# CATv1.net
KiCad netlist of a schematic drawn in EAGLE
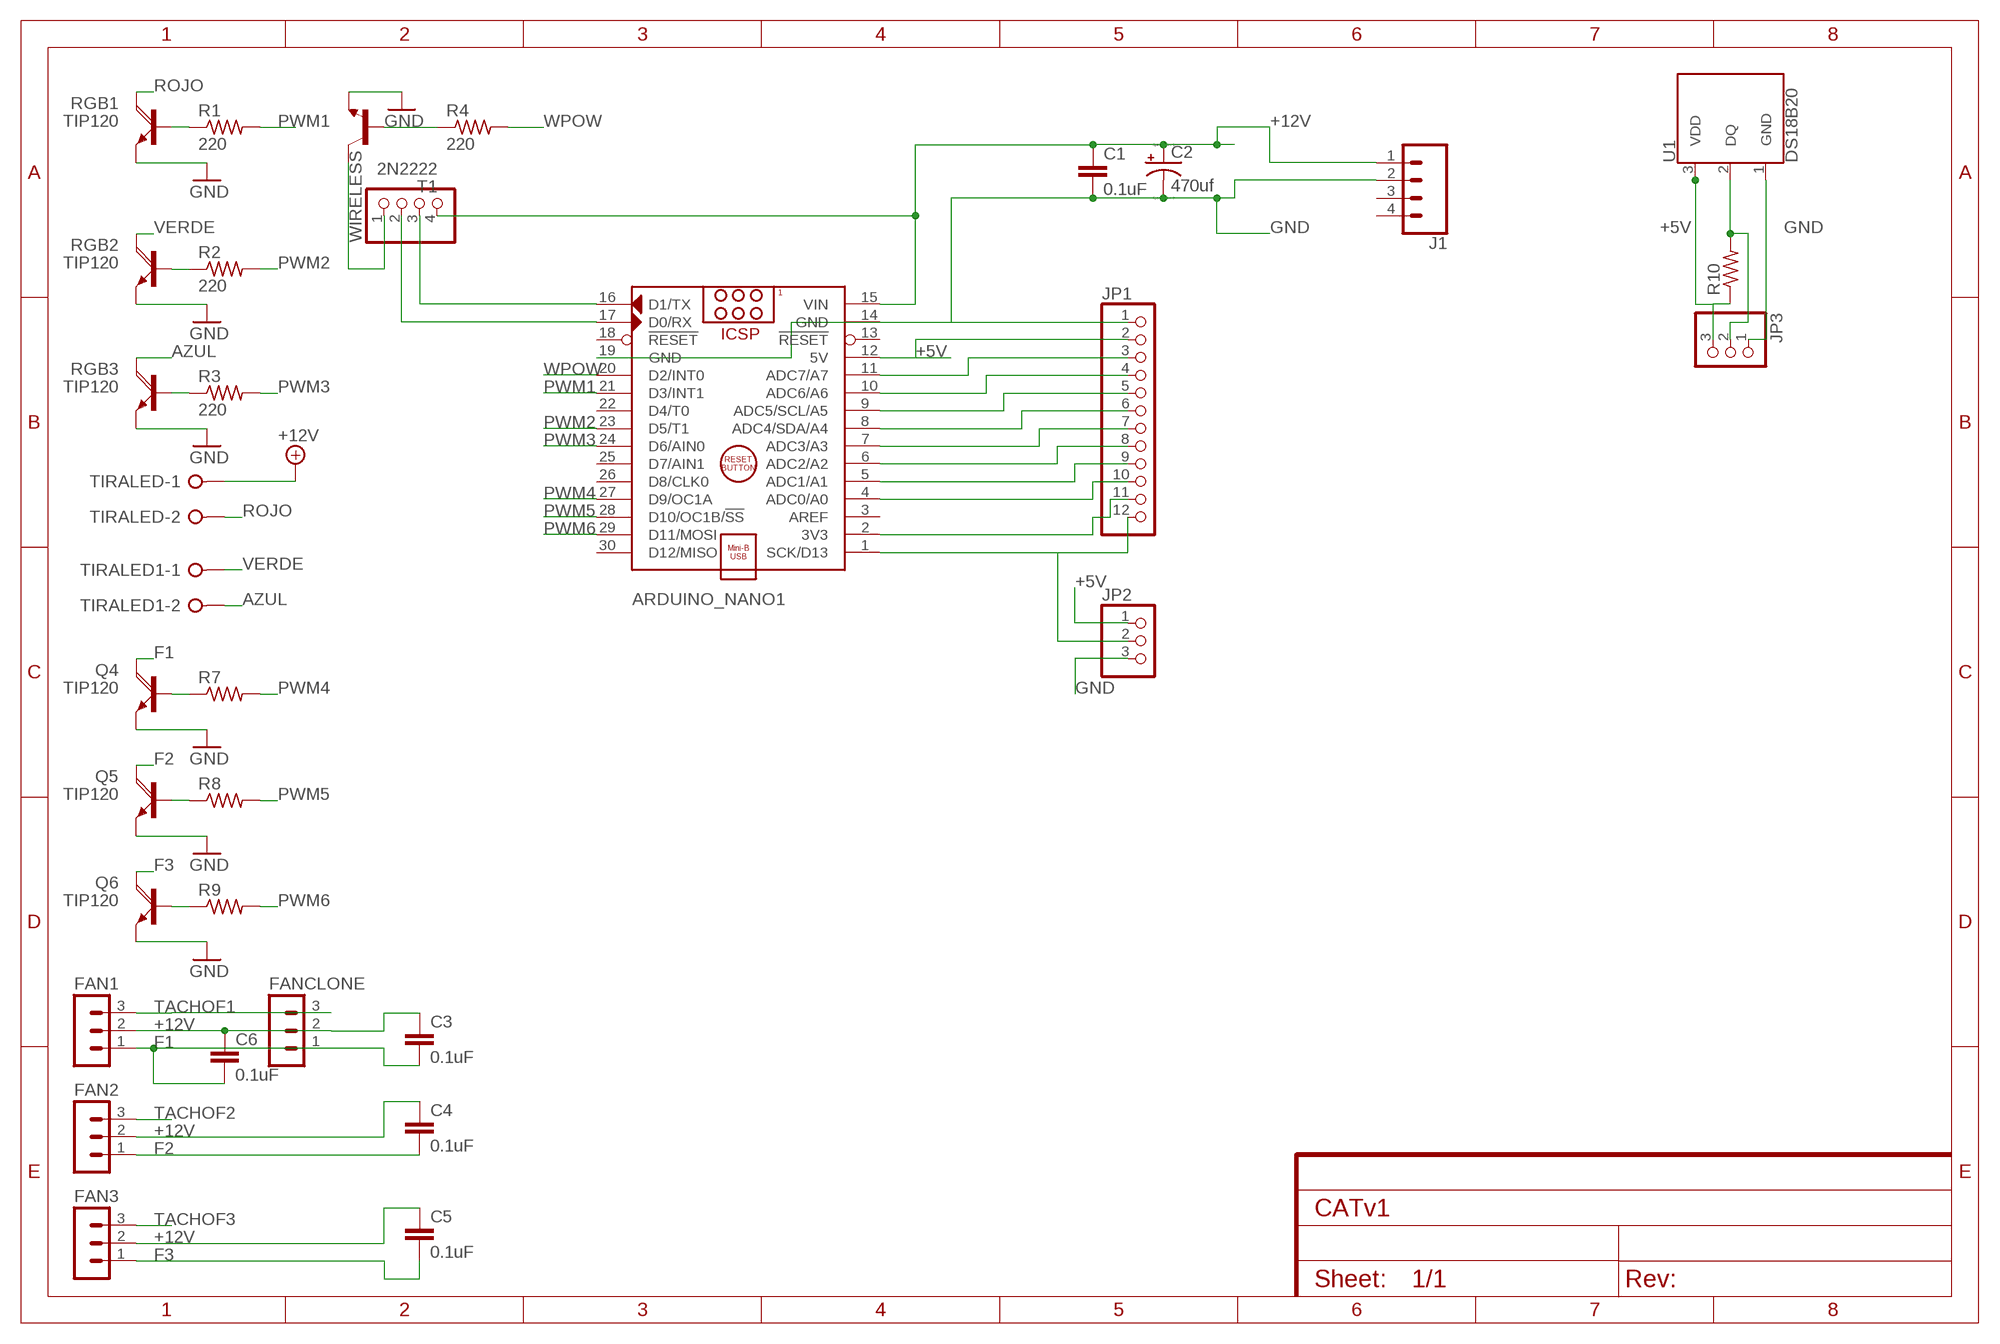
[diagram p0: schematic, sheet 1]

(export (version "E")
  (design (tool "Eeschema 10.0.6"))
  (components
    (comp (ref "ARDUINO_NANO1")
      (value "ARDUINO_NANO")
      (footprint "eagle-import:ARDUINO_NANO")
      (libsource (lib "eagle-import") (part "ARDUINO_NANO"))
    )
    (comp (ref "C1")
      (value "0.1uF")
      (footprint "eagle-import:CAP-PTH-SMALL-KIT")
      (libsource (lib "eagle-import") (part "0.1UF-KIT-EZ-50V-20%"))
    )
    (comp (ref "C2")
      (value "470uf")
      (footprint "eagle-import:E5-10,5")
      (libsource (lib "eagle-import") (part "CPOL-USE5-10.5"))
    )
    (comp (ref "C3")
      (value "0.1uF")
      (footprint "eagle-import:CAP-PTH-SMALL-KIT")
      (libsource (lib "eagle-import") (part "0.1UF-KIT-EZ-50V-20%"))
    )
    (comp (ref "C4")
      (value "0.1uF")
      (footprint "eagle-import:CAP-PTH-SMALL-KIT")
      (libsource (lib "eagle-import") (part "0.1UF-KIT-EZ-50V-20%"))
    )
    (comp (ref "C5")
      (value "0.1uF")
      (footprint "eagle-import:CAP-PTH-SMALL-KIT")
      (libsource (lib "eagle-import") (part "0.1UF-KIT-EZ-50V-20%"))
    )
    (comp (ref "C6")
      (value "0.1uF")
      (footprint "eagle-import:CAP-PTH-SMALL-KIT")
      (libsource (lib "eagle-import") (part "0.1UF-KIT-EZ-50V-20%"))
    )
    (comp (ref "FAN1")
      (value "MA03-1")
      (footprint "eagle-import:MA03-1")
      (libsource (lib "eagle-import") (part "MA03-1"))
    )
    (comp (ref "FAN2")
      (value "MA03-1")
      (footprint "eagle-import:MA03-1")
      (libsource (lib "eagle-import") (part "MA03-1"))
    )
    (comp (ref "FAN3")
      (value "MA03-1")
      (footprint "eagle-import:MA03-1")
      (libsource (lib "eagle-import") (part "MA03-1"))
    )
    (comp (ref "FANCLONE")
      (value "MA03-1")
      (footprint "eagle-import:MA03-1")
      (libsource (lib "eagle-import") (part "MA03-1"))
    )
    (comp (ref "J1")
      (value "CONN_04POLAR")
      (footprint "eagle-import:MOLEX-1X4")
      (libsource (lib "eagle-import") (part "CONN_04POLAR"))
    )
    (comp (ref "JP1")
      (value "PINHD-1X12")
      (footprint "eagle-import:1X12")
      (libsource (lib "eagle-import") (part "PINHD-1X12"))
    )
    (comp (ref "JP2")
      (value "PINHD-1X3")
      (footprint "eagle-import:1X03")
      (libsource (lib "eagle-import") (part "PINHD-1X3"))
    )
    (comp (ref "JP3")
      (value "PINHD-1X3")
      (footprint "eagle-import:1X03")
      (libsource (lib "eagle-import") (part "PINHD-1X3"))
    )
    (comp (ref "Q4")
      (value "TIP120")
      (footprint "eagle-import:TO220AH")
      (libsource (lib "eagle-import") (part "TIP120"))
    )
    (comp (ref "Q5")
      (value "TIP120")
      (footprint "eagle-import:TO220AH")
      (libsource (lib "eagle-import") (part "TIP120"))
    )
    (comp (ref "Q6")
      (value "TIP120")
      (footprint "eagle-import:TO220AH")
      (libsource (lib "eagle-import") (part "TIP120"))
    )
    (comp (ref "R1")
      (value "220")
      (footprint "eagle-import:0207_10")
      (libsource (lib "eagle-import") (part "R-US_0207/10"))
    )
    (comp (ref "R2")
      (value "220")
      (footprint "eagle-import:0207_10")
      (libsource (lib "eagle-import") (part "R-US_0207/10"))
    )
    (comp (ref "R3")
      (value "220")
      (footprint "eagle-import:0207_10")
      (libsource (lib "eagle-import") (part "R-US_0207/10"))
    )
    (comp (ref "R4")
      (value "220")
      (footprint "eagle-import:0207_12")
      (libsource (lib "eagle-import") (part "R-US_0207/12"))
    )
    (comp (ref "R7")
      (value "R-US_0207/10")
      (footprint "eagle-import:0207_10")
      (libsource (lib "eagle-import") (part "R-US_0207/10"))
    )
    (comp (ref "R8")
      (value "R-US_0207/10")
      (footprint "eagle-import:0207_10")
      (libsource (lib "eagle-import") (part "R-US_0207/10"))
    )
    (comp (ref "R9")
      (value "R-US_0207/10")
      (footprint "eagle-import:0207_10")
      (libsource (lib "eagle-import") (part "R-US_0207/10"))
    )
    (comp (ref "R10")
      (value "R-US_0207/10")
      (footprint "eagle-import:0207_10")
      (libsource (lib "eagle-import") (part "R-US_0207/10"))
    )
    (comp (ref "RGB1")
      (value "TIP120")
      (footprint "eagle-import:TO220AH")
      (libsource (lib "eagle-import") (part "TIP120"))
    )
    (comp (ref "RGB2")
      (value "TIP120")
      (footprint "eagle-import:TO220AH")
      (libsource (lib "eagle-import") (part "TIP120"))
    )
    (comp (ref "RGB3")
      (value "TIP120")
      (footprint "eagle-import:TO220AH")
      (libsource (lib "eagle-import") (part "TIP120"))
    )
    (comp (ref "T1")
      (value "2N2222")
      (footprint "eagle-import:TO92-EBC-OVAL")
      (libsource (lib "eagle-import") (part "2N2222"))
    )
    (comp (ref "TIRALED")
      (value "W237-02P")
      (footprint "eagle-import:W237-132")
      (libsource (lib "eagle-import") (part "W237-02P"))
    )
    (comp (ref "TIRALED1")
      (value "W237-02P")
      (footprint "eagle-import:W237-132")
      (libsource (lib "eagle-import") (part "W237-02P"))
    )
    (comp (ref "U1")
      (value "DS18B20")
      (footprint "eagle-import:TO-92-AMMO")
      (libsource (lib "eagle-import") (part "DS18B20"))
    )
    (comp (ref "WIRELESS")
      (value "PINHD-1X4")
      (footprint "eagle-import:1X04")
      (libsource (lib "eagle-import") (part "PINHD-1X4"))
    )
  )
  (nets
    (net (code "1") (name "+12V") (class "Default")
      (node (ref "ARDUINO_NANO1") (pin "15") (pinfunction "VIN_15") (pintype "power_in"))
      (node (ref "C1") (pin "1") (pinfunction "1_1") (pintype "passive"))
      (node (ref "C2") (pin "+") (pinfunction "+_+") (pintype "passive"))
      (node (ref "C3") (pin "1") (pinfunction "1_1") (pintype "passive"))
      (node (ref "C4") (pin "1") (pinfunction "1_1") (pintype "passive"))
      (node (ref "C5") (pin "1") (pinfunction "1_1") (pintype "passive"))
      (node (ref "C6") (pin "1") (pinfunction "1_1") (pintype "passive"))
      (node (ref "FAN1") (pin "2") (pinfunction "2_2") (pintype "passive"))
      (node (ref "FAN2") (pin "2") (pinfunction "2_2") (pintype "passive"))
      (node (ref "FAN3") (pin "2") (pinfunction "2_2") (pintype "passive"))
      (node (ref "FANCLONE") (pin "2") (pinfunction "2_2") (pintype "passive"))
      (node (ref "J1") (pin "1") (pinfunction "1_1") (pintype "passive"))
      (node (ref "TIRALED") (pin "1") (pinfunction "KL_1") (pintype "passive"))
      (node (ref "WIRELESS") (pin "4") (pinfunction "4_4") (pintype "passive"))
    )
    (net (code "2") (name "/+5V") (class "Default")
      (node (ref "ARDUINO_NANO1") (pin "12") (pinfunction "5V_12") (pintype "power_in"))
      (node (ref "JP1") (pin "2") (pinfunction "2_2") (pintype "passive"))
      (node (ref "JP2") (pin "1") (pinfunction "1_1") (pintype "passive"))
      (node (ref "JP3") (pin "3") (pinfunction "3_3") (pintype "passive"))
      (node (ref "R10") (pin "1") (pinfunction "1_1") (pintype "passive"))
      (node (ref "U1") (pin "3") (pinfunction "VDD_3") (pintype "power_in"))
    )
    (net (code "3") (name "/AZUL") (class "Default")
      (node (ref "RGB3") (pin "C") (pinfunction "C_C") (pintype "passive"))
      (node (ref "TIRALED1") (pin "2") (pinfunction "KL_2") (pintype "passive"))
    )
    (net (code "4") (name "/F1") (class "Default")
      (node (ref "C3") (pin "2") (pinfunction "2_2") (pintype "passive"))
      (node (ref "C6") (pin "2") (pinfunction "2_2") (pintype "passive"))
      (node (ref "FAN1") (pin "1") (pinfunction "1_1") (pintype "passive"))
      (node (ref "FANCLONE") (pin "1") (pinfunction "1_1") (pintype "passive"))
      (node (ref "Q4") (pin "C") (pinfunction "C_C") (pintype "passive"))
    )
    (net (code "5") (name "/F2") (class "Default")
      (node (ref "C4") (pin "2") (pinfunction "2_2") (pintype "passive"))
      (node (ref "FAN2") (pin "1") (pinfunction "1_1") (pintype "passive"))
      (node (ref "Q5") (pin "C") (pinfunction "C_C") (pintype "passive"))
    )
    (net (code "6") (name "/F3") (class "Default")
      (node (ref "C5") (pin "2") (pinfunction "2_2") (pintype "passive"))
      (node (ref "FAN3") (pin "1") (pinfunction "1_1") (pintype "passive"))
      (node (ref "Q6") (pin "C") (pinfunction "C_C") (pintype "passive"))
    )
    (net (code "7") (name "/PWM1") (class "Default")
      (node (ref "ARDUINO_NANO1") (pin "21") (pinfunction "D3/INT1_21") (pintype "bidirectional"))
      (node (ref "R1") (pin "2") (pinfunction "2_2") (pintype "passive"))
    )
    (net (code "8") (name "/PWM2") (class "Default")
      (node (ref "ARDUINO_NANO1") (pin "23") (pinfunction "D5/T1_23") (pintype "bidirectional"))
      (node (ref "R2") (pin "2") (pinfunction "2_2") (pintype "passive"))
    )
    (net (code "9") (name "/PWM3") (class "Default")
      (node (ref "ARDUINO_NANO1") (pin "24") (pinfunction "D6/AIN0_24") (pintype "bidirectional"))
      (node (ref "R3") (pin "2") (pinfunction "2_2") (pintype "passive"))
    )
    (net (code "10") (name "/PWM4") (class "Default")
      (node (ref "ARDUINO_NANO1") (pin "27") (pinfunction "D9/OC1A_27") (pintype "bidirectional"))
      (node (ref "R7") (pin "2") (pinfunction "2_2") (pintype "passive"))
    )
    (net (code "11") (name "/PWM5") (class "Default")
      (node (ref "ARDUINO_NANO1") (pin "28") (pinfunction "D10/OC1B/~{SS}_28") (pintype "bidirectional"))
      (node (ref "R8") (pin "2") (pinfunction "2_2") (pintype "passive"))
    )
    (net (code "12") (name "/PWM6") (class "Default")
      (node (ref "ARDUINO_NANO1") (pin "29") (pinfunction "D11/MOSI_29") (pintype "bidirectional"))
      (node (ref "R9") (pin "2") (pinfunction "2_2") (pintype "passive"))
    )
    (net (code "13") (name "/ROJO") (class "Default")
      (node (ref "RGB1") (pin "C") (pinfunction "C_C") (pintype "passive"))
      (node (ref "TIRALED") (pin "2") (pinfunction "KL_2") (pintype "passive"))
    )
    (net (code "14") (name "/TACHOF1") (class "Default")
      (node (ref "FAN1") (pin "3") (pinfunction "3_3") (pintype "passive"))
      (node (ref "FANCLONE") (pin "3") (pinfunction "3_3") (pintype "passive"))
    )
    (net (code "15") (name "/TACHOF2") (class "Default")
      (node (ref "FAN2") (pin "3") (pinfunction "3_3") (pintype "passive"))
    )
    (net (code "16") (name "/TACHOF3") (class "Default")
      (node (ref "FAN3") (pin "3") (pinfunction "3_3") (pintype "passive"))
    )
    (net (code "17") (name "/VERDE") (class "Default")
      (node (ref "RGB2") (pin "C") (pinfunction "C_C") (pintype "passive"))
      (node (ref "TIRALED1") (pin "1") (pinfunction "KL_1") (pintype "passive"))
    )
    (net (code "18") (name "/WPOW") (class "Default")
      (node (ref "ARDUINO_NANO1") (pin "20") (pinfunction "D2/INT0_20") (pintype "bidirectional"))
      (node (ref "R4") (pin "2") (pinfunction "2_2") (pintype "passive"))
    )
    (net (code "19") (name "GND") (class "Default")
      (node (ref "ARDUINO_NANO1") (pin "14") (pinfunction "GND_14") (pintype "power_in"))
      (node (ref "ARDUINO_NANO1") (pin "19") (pinfunction "GND_19") (pintype "power_in"))
      (node (ref "C1") (pin "2") (pinfunction "2_2") (pintype "passive"))
      (node (ref "C2") (pin "-") (pinfunction "-_-") (pintype "passive"))
      (node (ref "J1") (pin "2") (pinfunction "2_2") (pintype "passive"))
      (node (ref "JP1") (pin "1") (pinfunction "1_1") (pintype "passive"))
      (node (ref "JP2") (pin "3") (pinfunction "3_3") (pintype "passive"))
      (node (ref "JP3") (pin "1") (pinfunction "1_1") (pintype "passive"))
      (node (ref "Q4") (pin "E") (pinfunction "E_E") (pintype "passive"))
      (node (ref "Q5") (pin "E") (pinfunction "E_E") (pintype "passive"))
      (node (ref "Q6") (pin "E") (pinfunction "E_E") (pintype "passive"))
      (node (ref "RGB1") (pin "E") (pinfunction "E_E") (pintype "passive"))
      (node (ref "RGB2") (pin "E") (pinfunction "E_E") (pintype "passive"))
      (node (ref "RGB3") (pin "E") (pinfunction "E_E") (pintype "passive"))
      (node (ref "T1") (pin "E") (pinfunction "E_E") (pintype "passive"))
      (node (ref "U1") (pin "1") (pinfunction "GND_1") (pintype "power_in"))
    )
    (net (code "20") (name "Net-(ARDUINO_NANO1-3V3)") (class "Default")
      (node (ref "ARDUINO_NANO1") (pin "2") (pinfunction "3V3_2") (pintype "output"))
      (node (ref "JP1") (pin "11") (pinfunction "11_11") (pintype "passive"))
    )
    (net (code "21") (name "Net-(ARDUINO_NANO1-ADC0{slash}A0)") (class "Default")
      (node (ref "ARDUINO_NANO1") (pin "4") (pinfunction "ADC0/A0_4") (pintype "bidirectional"))
      (node (ref "JP1") (pin "10") (pinfunction "10_10") (pintype "passive"))
    )
    (net (code "22") (name "Net-(ARDUINO_NANO1-ADC1{slash}A1)") (class "Default")
      (node (ref "ARDUINO_NANO1") (pin "5") (pinfunction "ADC1/A1_5") (pintype "bidirectional"))
      (node (ref "JP1") (pin "9") (pinfunction "9_9") (pintype "passive"))
    )
    (net (code "23") (name "Net-(ARDUINO_NANO1-ADC2{slash}A2)") (class "Default")
      (node (ref "ARDUINO_NANO1") (pin "6") (pinfunction "ADC2/A2_6") (pintype "bidirectional"))
      (node (ref "JP1") (pin "8") (pinfunction "8_8") (pintype "passive"))
    )
    (net (code "24") (name "Net-(ARDUINO_NANO1-ADC3{slash}A3)") (class "Default")
      (node (ref "ARDUINO_NANO1") (pin "7") (pinfunction "ADC3/A3_7") (pintype "bidirectional"))
      (node (ref "JP1") (pin "7") (pinfunction "7_7") (pintype "passive"))
    )
    (net (code "25") (name "Net-(ARDUINO_NANO1-ADC4{slash}SDA{slash}A4)") (class "Default")
      (node (ref "ARDUINO_NANO1") (pin "8") (pinfunction "ADC4/SDA/A4_8") (pintype "bidirectional"))
      (node (ref "JP1") (pin "6") (pinfunction "6_6") (pintype "passive"))
    )
    (net (code "26") (name "Net-(ARDUINO_NANO1-ADC5{slash}SCL{slash}A5)") (class "Default")
      (node (ref "ARDUINO_NANO1") (pin "9") (pinfunction "ADC5/SCL/A5_9") (pintype "bidirectional"))
      (node (ref "JP1") (pin "5") (pinfunction "5_5") (pintype "passive"))
    )
    (net (code "27") (name "Net-(ARDUINO_NANO1-ADC6{slash}A6)") (class "Default")
      (node (ref "ARDUINO_NANO1") (pin "10") (pinfunction "ADC6/A6_10") (pintype "bidirectional"))
      (node (ref "JP1") (pin "4") (pinfunction "4_4") (pintype "passive"))
    )
    (net (code "28") (name "Net-(ARDUINO_NANO1-ADC7{slash}A7)") (class "Default")
      (node (ref "ARDUINO_NANO1") (pin "11") (pinfunction "ADC7/A7_11") (pintype "bidirectional"))
      (node (ref "JP1") (pin "3") (pinfunction "3_3") (pintype "passive"))
    )
    (net (code "29") (name "Net-(ARDUINO_NANO1-D0{slash}RX)") (class "Default")
      (node (ref "ARDUINO_NANO1") (pin "17") (pinfunction "D0/RX_17") (pintype "bidirectional"))
      (node (ref "WIRELESS") (pin "2") (pinfunction "2_2") (pintype "passive"))
    )
    (net (code "30") (name "Net-(ARDUINO_NANO1-D1{slash}TX)") (class "Default")
      (node (ref "ARDUINO_NANO1") (pin "16") (pinfunction "D1/TX_16") (pintype "bidirectional"))
      (node (ref "WIRELESS") (pin "3") (pinfunction "3_3") (pintype "passive"))
    )
    (net (code "31") (name "Net-(ARDUINO_NANO1-SCK{slash}D13)") (class "Default")
      (node (ref "ARDUINO_NANO1") (pin "1") (pinfunction "SCK/D13_1") (pintype "bidirectional"))
      (node (ref "JP1") (pin "12") (pinfunction "12_12") (pintype "passive"))
      (node (ref "JP2") (pin "2") (pinfunction "2_2") (pintype "passive"))
    )
    (net (code "32") (name "Net-(Q4-PadB)") (class "Default")
      (node (ref "Q4") (pin "B") (pinfunction "B_B") (pintype "passive"))
      (node (ref "R7") (pin "1") (pinfunction "1_1") (pintype "passive"))
    )
    (net (code "33") (name "Net-(Q5-PadB)") (class "Default")
      (node (ref "Q5") (pin "B") (pinfunction "B_B") (pintype "passive"))
      (node (ref "R8") (pin "1") (pinfunction "1_1") (pintype "passive"))
    )
    (net (code "34") (name "Net-(Q6-PadB)") (class "Default")
      (node (ref "Q6") (pin "B") (pinfunction "B_B") (pintype "passive"))
      (node (ref "R9") (pin "1") (pinfunction "1_1") (pintype "passive"))
    )
    (net (code "35") (name "Net-(R1-Pad1)") (class "Default")
      (node (ref "R1") (pin "1") (pinfunction "1_1") (pintype "passive"))
      (node (ref "RGB1") (pin "B") (pinfunction "B_B") (pintype "passive"))
    )
    (net (code "36") (name "Net-(R2-Pad1)") (class "Default")
      (node (ref "R2") (pin "1") (pinfunction "1_1") (pintype "passive"))
      (node (ref "RGB2") (pin "B") (pinfunction "B_B") (pintype "passive"))
    )
    (net (code "37") (name "Net-(R3-Pad1)") (class "Default")
      (node (ref "R3") (pin "1") (pinfunction "1_1") (pintype "passive"))
      (node (ref "RGB3") (pin "B") (pinfunction "B_B") (pintype "passive"))
    )
    (net (code "38") (name "Net-(R4-Pad1)") (class "Default")
      (node (ref "R4") (pin "1") (pinfunction "1_1") (pintype "passive"))
      (node (ref "T1") (pin "B") (pinfunction "B_B") (pintype "passive"))
    )
    (net (code "39") (name "Net-(T1-PadC)") (class "Default")
      (node (ref "T1") (pin "C") (pinfunction "C_C") (pintype "passive"))
      (node (ref "WIRELESS") (pin "1") (pinfunction "1_1") (pintype "passive"))
    )
    (net (code "40") (name "Net-(U1-DQ)") (class "Default")
      (node (ref "JP3") (pin "2") (pinfunction "2_2") (pintype "passive"))
      (node (ref "R10") (pin "2") (pinfunction "2_2") (pintype "passive"))
      (node (ref "U1") (pin "2") (pinfunction "DQ_2") (pintype "bidirectional"))
    )
    (net (code "41") (name "unconnected-(ARDUINO_NANO1-AREF-Pad3)") (class "Default")
      (node (ref "ARDUINO_NANO1") (pin "3") (pinfunction "AREF_3") (pintype "input"))
    )
    (net (code "42") (name "unconnected-(ARDUINO_NANO1-D4{slash}T0-Pad22)") (class "Default")
      (node (ref "ARDUINO_NANO1") (pin "22") (pinfunction "D4/T0_22") (pintype "bidirectional"))
    )
    (net (code "43") (name "unconnected-(ARDUINO_NANO1-D7{slash}AIN1-Pad25)") (class "Default")
      (node (ref "ARDUINO_NANO1") (pin "25") (pinfunction "D7/AIN1_25") (pintype "bidirectional"))
    )
    (net (code "44") (name "unconnected-(ARDUINO_NANO1-D8{slash}CLK0-Pad26)") (class "Default")
      (node (ref "ARDUINO_NANO1") (pin "26") (pinfunction "D8/CLK0_26") (pintype "bidirectional"))
    )
    (net (code "45") (name "unconnected-(ARDUINO_NANO1-D12{slash}MISO-Pad30)") (class "Default")
      (node (ref "ARDUINO_NANO1") (pin "30") (pinfunction "D12/MISO_30") (pintype "bidirectional"))
    )
    (net (code "46") (name "unconnected-(ARDUINO_NANO1-~{RESET}-Pad13)") (class "Default")
      (node (ref "ARDUINO_NANO1") (pin "13") (pinfunction "~{RESET}_13") (pintype "input"))
    )
    (net (code "47") (name "unconnected-(ARDUINO_NANO1-~{RESET}-Pad18)") (class "Default")
      (node (ref "ARDUINO_NANO1") (pin "18") (pinfunction "~{RESET}_18") (pintype "input"))
    )
    (net (code "48") (name "unconnected-(J1-Pad3)") (class "Default")
      (node (ref "J1") (pin "3") (pinfunction "3_3") (pintype "passive"))
    )
    (net (code "49") (name "unconnected-(J1-Pad4)") (class "Default")
      (node (ref "J1") (pin "4") (pinfunction "4_4") (pintype "passive"))
    )
  )
)
